# Socket.net
KiCad netlist of a schematic drawn in EAGLE
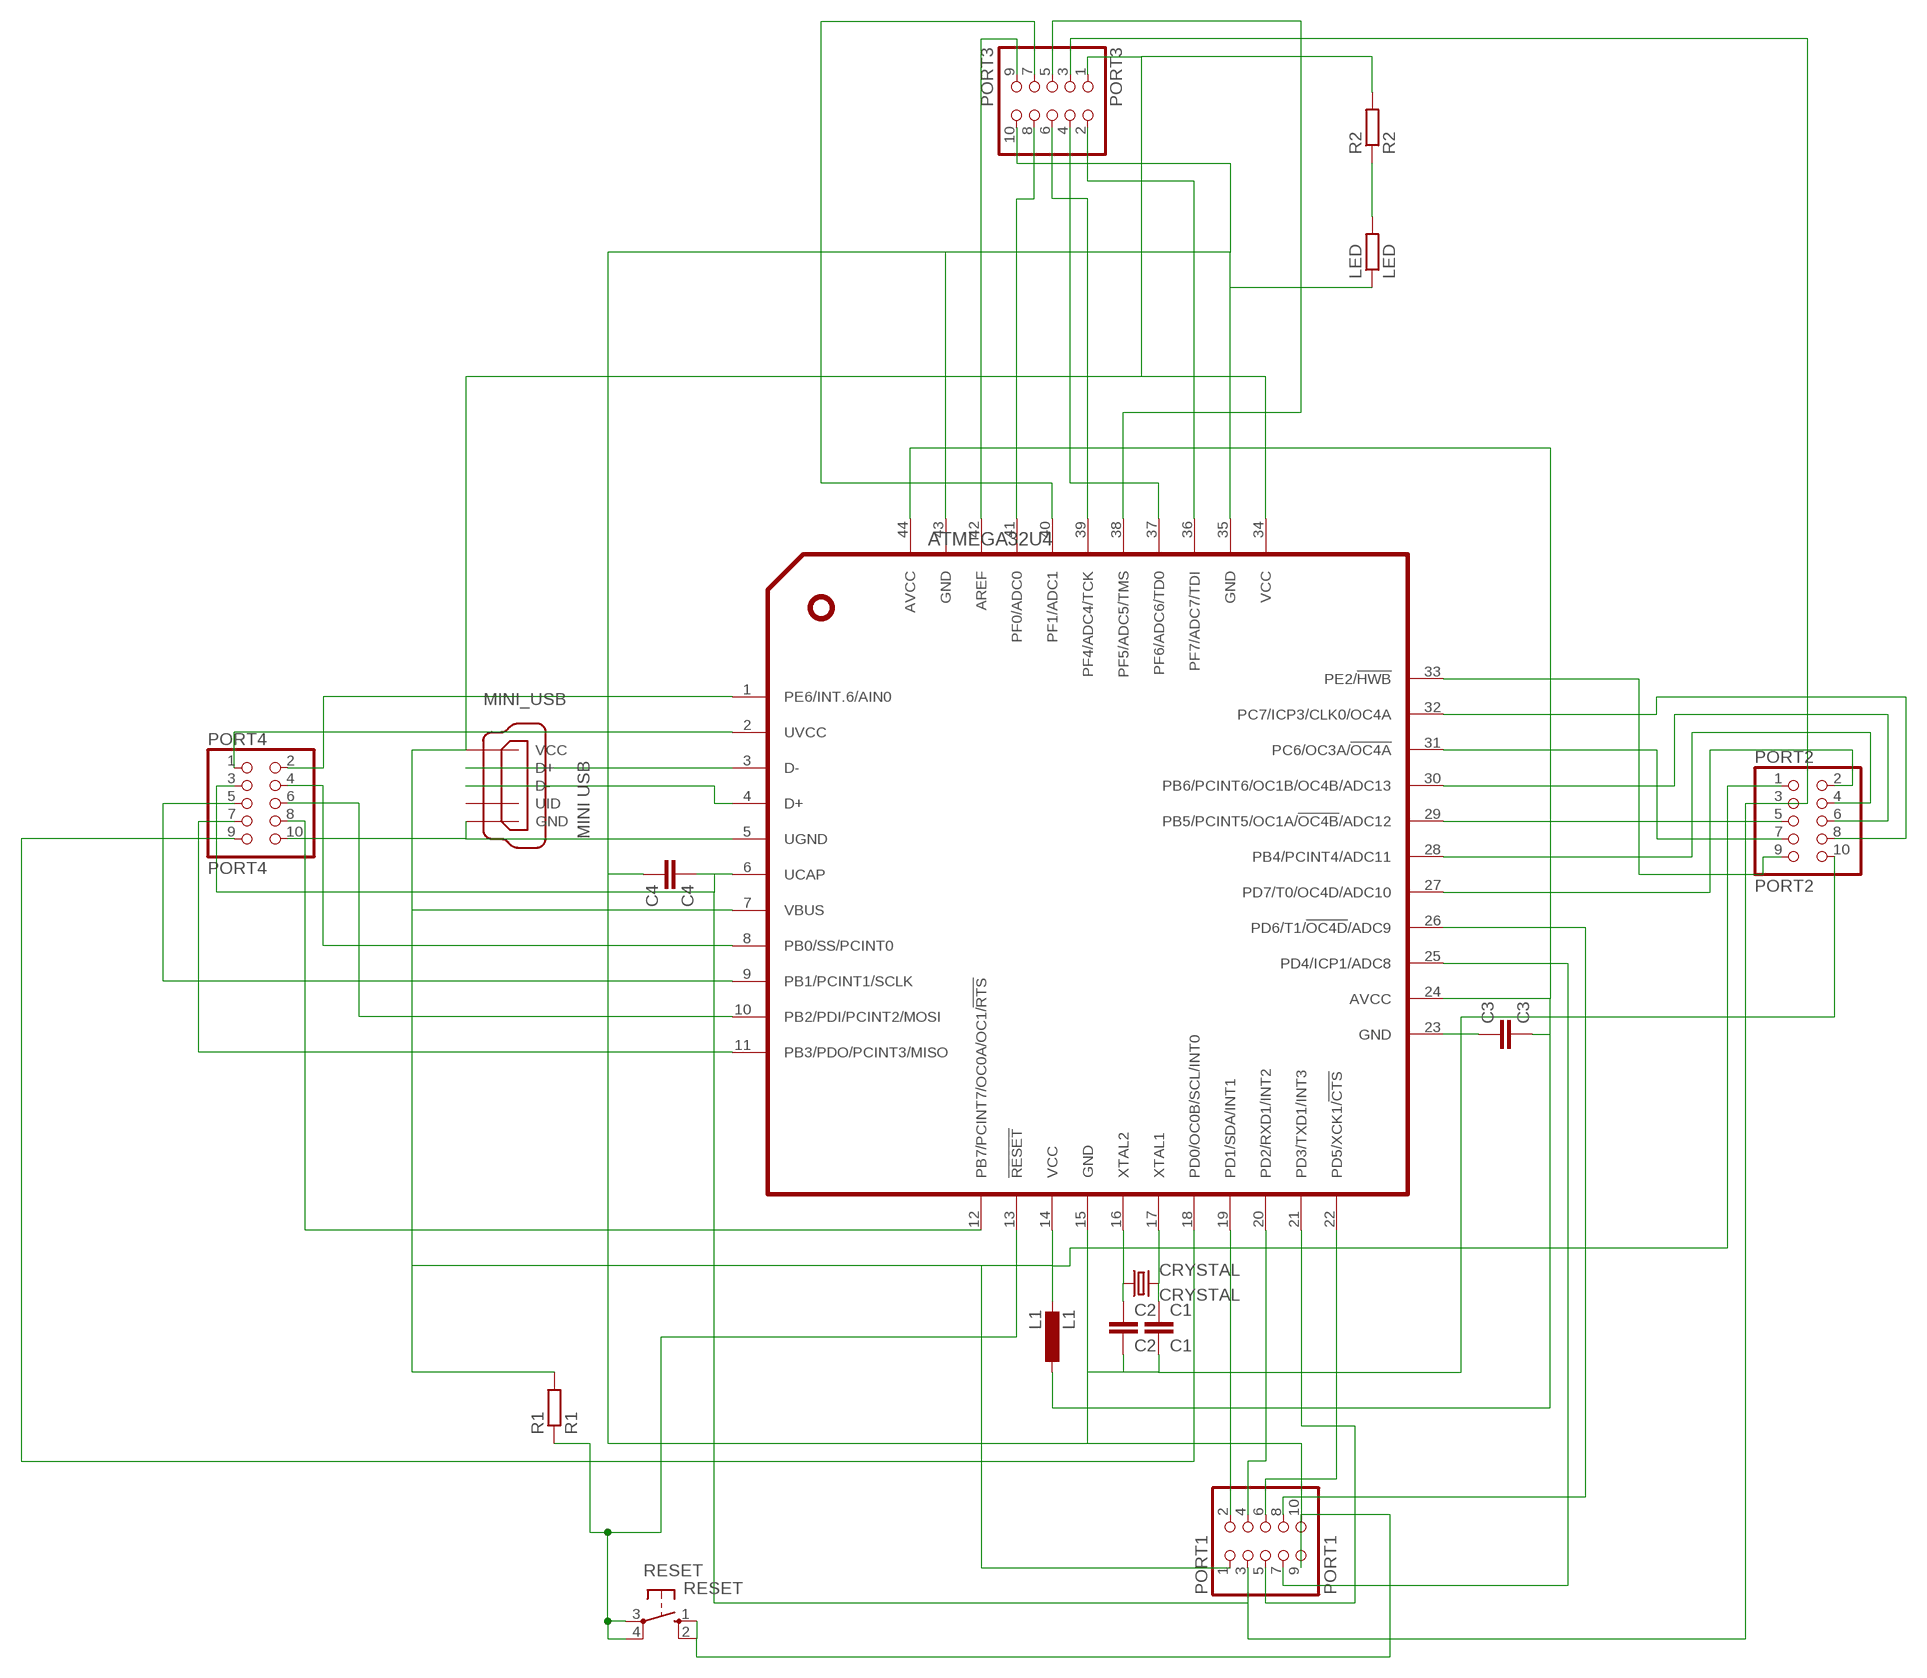
[diagram p0: schematic, sheet 1]

(export (version "E")
  (design (tool "Eeschema 10.0.6"))
  (components
    (comp (ref "ATMEGA32U4")
      (value "ATMEGA32U4")
      (footprint "eagle-import:TQFP44")
      (libsource (lib "eagle-import") (part "AT-MEGA16/32-U4"))
    )
    (comp (ref "C1")
      (value "C1")
      (footprint "eagle-import:C0603")
      (libsource (lib "eagle-import") (part "C-EUC0603"))
    )
    (comp (ref "C2")
      (value "C2")
      (footprint "eagle-import:C0603")
      (libsource (lib "eagle-import") (part "C-EUC0603"))
    )
    (comp (ref "C3")
      (value "C3")
      (footprint "eagle-import:C0603")
      (libsource (lib "eagle-import") (part "C-EUC0603"))
    )
    (comp (ref "C4")
      (value "C4")
      (footprint "eagle-import:C0603")
      (libsource (lib "eagle-import") (part "C-EUC0603"))
    )
    (comp (ref "CRYSTAL")
      (value "CRYSTAL")
      (footprint "eagle-import:HC49UP")
      (libsource (lib "eagle-import") (part "CRYSTALHC49UP"))
    )
    (comp (ref "L1")
      (value "L1")
      (footprint "eagle-import:L2012C")
      (libsource (lib "eagle-import") (part "L-EUL2012C"))
    )
    (comp (ref "LED")
      (value "LED")
      (footprint "eagle-import:R0603")
      (libsource (lib "eagle-import") (part "R-EU_R0603"))
    )
    (comp (ref "MINI_USB")
      (value "MINI USB")
      (footprint "eagle-import:UX60-MB-5S8")
      (libsource (lib "eagle-import") (part "MINI-USB-UX60-MB-5S8"))
    )
    (comp (ref "PORT1")
      (value "PORT1")
      (footprint "eagle-import:2X05")
      (libsource (lib "eagle-import") (part "PINHD-2X5"))
    )
    (comp (ref "PORT2")
      (value "PORT2")
      (footprint "eagle-import:2X05")
      (libsource (lib "eagle-import") (part "PINHD-2X5"))
    )
    (comp (ref "PORT3")
      (value "PORT3")
      (footprint "eagle-import:2X05")
      (libsource (lib "eagle-import") (part "PINHD-2X5"))
    )
    (comp (ref "PORT4")
      (value "PORT4")
      (footprint "eagle-import:2X05")
      (libsource (lib "eagle-import") (part "PINHD-2X5"))
    )
    (comp (ref "R1")
      (value "R1")
      (footprint "eagle-import:R0603")
      (libsource (lib "eagle-import") (part "R-EU_R0603"))
    )
    (comp (ref "R2")
      (value "R2")
      (footprint "eagle-import:R0603")
      (libsource (lib "eagle-import") (part "R-EU_R0603"))
    )
    (comp (ref "RESET")
      (value "RESET")
      (footprint "eagle-import:B3F-10XX")
      (fields (field (name "MPN") "B3F-1000"))
      (libsource (lib "eagle-import") (part "10-XX"))
    )
  )
  (nets
    (net (code "1") (name "Net-(ATMEGA32U4-AREF)") (class "Default")
      (node (ref "ATMEGA32U4") (pin "42") (pinfunction "AREF_42") (pintype "bidirectional"))
      (node (ref "PORT3") (pin "9") (pinfunction "9_9") (pintype "passive"))
    )
    (net (code "2") (name "Net-(ATMEGA32U4-AVCC-Pad24)") (class "Default")
      (node (ref "ATMEGA32U4") (pin "24") (pinfunction "AVCC_24") (pintype "power_in"))
      (node (ref "ATMEGA32U4") (pin "44") (pinfunction "AVCC_44") (pintype "power_in"))
      (node (ref "C3") (pin "2") (pinfunction "2_2") (pintype "passive"))
      (node (ref "L1") (pin "1") (pinfunction "1_1") (pintype "passive"))
    )
    (net (code "3") (name "Net-(ATMEGA32U4-D+)") (class "Default")
      (node (ref "ATMEGA32U4") (pin "4") (pinfunction "D+_4") (pintype "bidirectional"))
      (node (ref "MINI_USB") (pin "D-") (pinfunction "D-_D-") (pintype "input"))
    )
    (net (code "4") (name "Net-(ATMEGA32U4-D-)") (class "Default")
      (node (ref "ATMEGA32U4") (pin "3") (pinfunction "D-_3") (pintype "bidirectional"))
      (node (ref "MINI_USB") (pin "D+") (pinfunction "D+_D+") (pintype "input"))
    )
    (net (code "5") (name "Net-(ATMEGA32U4-PB0{slash}SS{slash}PCINT0)") (class "Default")
      (node (ref "ATMEGA32U4") (pin "8") (pinfunction "PB0/SS/PCINT0_8") (pintype "bidirectional"))
      (node (ref "PORT4") (pin "4") (pinfunction "4_4") (pintype "passive"))
    )
    (net (code "6") (name "Net-(ATMEGA32U4-PB1{slash}PCINT1{slash}SCLK)") (class "Default")
      (node (ref "ATMEGA32U4") (pin "9") (pinfunction "PB1/PCINT1/SCLK_9") (pintype "bidirectional"))
      (node (ref "PORT4") (pin "5") (pinfunction "5_5") (pintype "passive"))
    )
    (net (code "7") (name "Net-(ATMEGA32U4-PB2{slash}PDI{slash}PCINT2{slash}MOSI)") (class "Default")
      (node (ref "ATMEGA32U4") (pin "10") (pinfunction "PB2/PDI/PCINT2/MOSI_10") (pintype "bidirectional"))
      (node (ref "PORT4") (pin "6") (pinfunction "6_6") (pintype "passive"))
    )
    (net (code "8") (name "Net-(ATMEGA32U4-PB3{slash}PDO{slash}PCINT3{slash}MISO)") (class "Default")
      (node (ref "ATMEGA32U4") (pin "11") (pinfunction "PB3/PDO/PCINT3/MISO_11") (pintype "bidirectional"))
      (node (ref "PORT4") (pin "7") (pinfunction "7_7") (pintype "passive"))
    )
    (net (code "9") (name "Net-(ATMEGA32U4-PB4{slash}PCINT4{slash}ADC11)") (class "Default")
      (node (ref "ATMEGA32U4") (pin "28") (pinfunction "PB4/PCINT4/ADC11_28") (pintype "bidirectional"))
      (node (ref "PORT2") (pin "4") (pinfunction "4_4") (pintype "passive"))
    )
    (net (code "10") (name "Net-(ATMEGA32U4-PB5{slash}PCINT5{slash}OC1A{slash}~{OC4B}{slash}ADC12)") (class "Default")
      (node (ref "ATMEGA32U4") (pin "29") (pinfunction "PB5/PCINT5/OC1A/~{OC4B}/ADC12_29") (pintype "bidirectional"))
      (node (ref "PORT2") (pin "5") (pinfunction "5_5") (pintype "passive"))
    )
    (net (code "11") (name "Net-(ATMEGA32U4-PB6{slash}PCINT6{slash}OC1B{slash}OC4B{slash}ADC13)") (class "Default")
      (node (ref "ATMEGA32U4") (pin "30") (pinfunction "PB6/PCINT6/OC1B/OC4B/ADC13_30") (pintype "bidirectional"))
      (node (ref "PORT2") (pin "6") (pinfunction "6_6") (pintype "passive"))
    )
    (net (code "12") (name "Net-(ATMEGA32U4-PB7{slash}PCINT7{slash}OC0A{slash}OC1{slash}~{RTS})") (class "Default")
      (node (ref "ATMEGA32U4") (pin "12") (pinfunction "PB7/PCINT7/OC0A/OC1/~{RTS}_12") (pintype "bidirectional"))
      (node (ref "PORT4") (pin "8") (pinfunction "8_8") (pintype "passive"))
    )
    (net (code "13") (name "Net-(ATMEGA32U4-PC6{slash}OC3A{slash}~{OC4A})") (class "Default")
      (node (ref "ATMEGA32U4") (pin "31") (pinfunction "PC6/OC3A/~{OC4A}_31") (pintype "bidirectional"))
      (node (ref "PORT2") (pin "7") (pinfunction "7_7") (pintype "passive"))
    )
    (net (code "14") (name "Net-(ATMEGA32U4-PC7{slash}ICP3{slash}CLK0{slash}OC4A)") (class "Default")
      (node (ref "ATMEGA32U4") (pin "32") (pinfunction "PC7/ICP3/CLK0/OC4A_32") (pintype "bidirectional"))
      (node (ref "PORT2") (pin "8") (pinfunction "8_8") (pintype "passive"))
    )
    (net (code "15") (name "Net-(ATMEGA32U4-PD0{slash}OC0B{slash}SCL{slash}INT0)") (class "Default")
      (node (ref "ATMEGA32U4") (pin "18") (pinfunction "PD0/OC0B/SCL/INT0_18") (pintype "bidirectional"))
      (node (ref "PORT4") (pin "9") (pinfunction "9_9") (pintype "passive"))
    )
    (net (code "16") (name "Net-(ATMEGA32U4-PD1{slash}SDA{slash}INT1)") (class "Default")
      (node (ref "ATMEGA32U4") (pin "19") (pinfunction "PD1/SDA/INT1_19") (pintype "bidirectional"))
      (node (ref "PORT1") (pin "2") (pinfunction "2_2") (pintype "passive"))
    )
    (net (code "17") (name "Net-(ATMEGA32U4-PD2{slash}RXD1{slash}INT2)") (class "Default")
      (node (ref "ATMEGA32U4") (pin "20") (pinfunction "PD2/RXD1/INT2_20") (pintype "bidirectional"))
      (node (ref "PORT1") (pin "4") (pinfunction "4_4") (pintype "passive"))
    )
    (net (code "18") (name "Net-(ATMEGA32U4-PD3{slash}TXD1{slash}INT3)") (class "Default")
      (node (ref "ATMEGA32U4") (pin "21") (pinfunction "PD3/TXD1/INT3_21") (pintype "bidirectional"))
      (node (ref "PORT1") (pin "5") (pinfunction "5_5") (pintype "passive"))
    )
    (net (code "19") (name "Net-(ATMEGA32U4-PD4{slash}ICP1{slash}ADC8)") (class "Default")
      (node (ref "ATMEGA32U4") (pin "25") (pinfunction "PD4/ICP1/ADC8_25") (pintype "bidirectional"))
      (node (ref "PORT1") (pin "7") (pinfunction "7_7") (pintype "passive"))
    )
    (net (code "20") (name "Net-(ATMEGA32U4-PD5{slash}XCK1{slash}~{CTS})") (class "Default")
      (node (ref "ATMEGA32U4") (pin "22") (pinfunction "PD5/XCK1/~{CTS}_22") (pintype "bidirectional"))
      (node (ref "PORT1") (pin "6") (pinfunction "6_6") (pintype "passive"))
    )
    (net (code "21") (name "Net-(ATMEGA32U4-PD6{slash}T1{slash}~{OC4D}{slash}ADC9)") (class "Default")
      (node (ref "ATMEGA32U4") (pin "26") (pinfunction "PD6/T1/~{OC4D}/ADC9_26") (pintype "bidirectional"))
      (node (ref "PORT1") (pin "8") (pinfunction "8_8") (pintype "passive"))
    )
    (net (code "22") (name "Net-(ATMEGA32U4-PD7{slash}T0{slash}OC4D{slash}ADC10)") (class "Default")
      (node (ref "ATMEGA32U4") (pin "27") (pinfunction "PD7/T0/OC4D/ADC10_27") (pintype "bidirectional"))
      (node (ref "PORT2") (pin "2") (pinfunction "2_2") (pintype "passive"))
    )
    (net (code "23") (name "Net-(ATMEGA32U4-PE2{slash}~{HWB})") (class "Default")
      (node (ref "ATMEGA32U4") (pin "33") (pinfunction "PE2/~{HWB}_33") (pintype "bidirectional"))
      (node (ref "PORT2") (pin "9") (pinfunction "9_9") (pintype "passive"))
    )
    (net (code "24") (name "Net-(ATMEGA32U4-PE6{slash}INT.6{slash}AIN0)") (class "Default")
      (node (ref "ATMEGA32U4") (pin "1") (pinfunction "PE6/INT.6/AIN0_1") (pintype "bidirectional"))
      (node (ref "PORT4") (pin "2") (pinfunction "2_2") (pintype "passive"))
    )
    (net (code "25") (name "Net-(ATMEGA32U4-PF0{slash}ADC0)") (class "Default")
      (node (ref "ATMEGA32U4") (pin "41") (pinfunction "PF0/ADC0_41") (pintype "bidirectional"))
      (node (ref "PORT3") (pin "8") (pinfunction "8_8") (pintype "passive"))
    )
    (net (code "26") (name "Net-(ATMEGA32U4-PF1{slash}ADC1)") (class "Default")
      (node (ref "ATMEGA32U4") (pin "40") (pinfunction "PF1/ADC1_40") (pintype "bidirectional"))
      (node (ref "PORT3") (pin "7") (pinfunction "7_7") (pintype "passive"))
    )
    (net (code "27") (name "Net-(ATMEGA32U4-PF4{slash}ADC4{slash}TCK)") (class "Default")
      (node (ref "ATMEGA32U4") (pin "39") (pinfunction "PF4/ADC4/TCK_39") (pintype "bidirectional"))
      (node (ref "PORT3") (pin "6") (pinfunction "6_6") (pintype "passive"))
    )
    (net (code "28") (name "Net-(ATMEGA32U4-PF5{slash}ADC5{slash}TMS)") (class "Default")
      (node (ref "ATMEGA32U4") (pin "38") (pinfunction "PF5/ADC5/TMS_38") (pintype "bidirectional"))
      (node (ref "PORT3") (pin "5") (pinfunction "5_5") (pintype "passive"))
    )
    (net (code "29") (name "Net-(ATMEGA32U4-PF6{slash}ADC6{slash}TD0)") (class "Default")
      (node (ref "ATMEGA32U4") (pin "37") (pinfunction "PF6/ADC6/TD0_37") (pintype "bidirectional"))
      (node (ref "PORT3") (pin "4") (pinfunction "4_4") (pintype "passive"))
    )
    (net (code "30") (name "Net-(ATMEGA32U4-PF7{slash}ADC7{slash}TDI)") (class "Default")
      (node (ref "ATMEGA32U4") (pin "36") (pinfunction "PF7/ADC7/TDI_36") (pintype "bidirectional"))
      (node (ref "PORT3") (pin "2") (pinfunction "2_2") (pintype "passive"))
    )
    (net (code "31") (name "Net-(ATMEGA32U4-UCAP)") (class "Default")
      (node (ref "ATMEGA32U4") (pin "6") (pinfunction "UCAP_6") (pintype "bidirectional"))
      (node (ref "C4") (pin "1") (pinfunction "1_1") (pintype "passive"))
      (node (ref "PORT1") (pin "3") (pinfunction "3_3") (pintype "passive"))
      (node (ref "PORT2") (pin "3") (pinfunction "3_3") (pintype "passive"))
      (node (ref "PORT3") (pin "3") (pinfunction "3_3") (pintype "passive"))
      (node (ref "PORT4") (pin "3") (pinfunction "3_3") (pintype "passive"))
    )
    (net (code "32") (name "Net-(ATMEGA32U4-UGND)") (class "Default")
      (node (ref "ATMEGA32U4") (pin "15") (pinfunction "GND_15") (pintype "power_in"))
      (node (ref "ATMEGA32U4") (pin "23") (pinfunction "GND_23") (pintype "power_in"))
      (node (ref "ATMEGA32U4") (pin "35") (pinfunction "GND_35") (pintype "power_in"))
      (node (ref "ATMEGA32U4") (pin "43") (pinfunction "GND_43") (pintype "power_in"))
      (node (ref "ATMEGA32U4") (pin "5") (pinfunction "UGND_5") (pintype "power_in"))
      (node (ref "C1") (pin "2") (pinfunction "2_2") (pintype "passive"))
      (node (ref "C2") (pin "2") (pinfunction "2_2") (pintype "passive"))
      (node (ref "C3") (pin "1") (pinfunction "1_1") (pintype "passive"))
      (node (ref "C4") (pin "2") (pinfunction "2_2") (pintype "passive"))
      (node (ref "LED") (pin "1") (pinfunction "1_1") (pintype "passive"))
      (node (ref "MINI_USB") (pin "GND") (pinfunction "GND_GND") (pintype "input"))
      (node (ref "MINI_USB") (pin "GND1") (pinfunction "GND_GND1") (pintype "input"))
      (node (ref "MINI_USB") (pin "GND2") (pinfunction "GND_GND2") (pintype "input"))
      (node (ref "MINI_USB") (pin "GND3") (pinfunction "GND_GND3") (pintype "input"))
      (node (ref "MINI_USB") (pin "GND4") (pinfunction "GND_GND4") (pintype "input"))
      (node (ref "PORT1") (pin "10") (pinfunction "10_10") (pintype "passive"))
      (node (ref "PORT1") (pin "9") (pinfunction "9_9") (pintype "passive"))
      (node (ref "PORT2") (pin "10") (pinfunction "10_10") (pintype "passive"))
      (node (ref "PORT3") (pin "10") (pinfunction "10_10") (pintype "passive"))
      (node (ref "PORT4") (pin "10") (pinfunction "10_10") (pintype "passive"))
      (node (ref "RESET") (pin "1") (pinfunction "S_1") (pintype "passive"))
      (node (ref "RESET") (pin "2") (pinfunction "S1_2") (pintype "passive"))
    )
    (net (code "33") (name "Net-(ATMEGA32U4-UVCC)") (class "Default")
      (node (ref "ATMEGA32U4") (pin "14") (pinfunction "VCC_14") (pintype "power_in"))
      (node (ref "ATMEGA32U4") (pin "2") (pinfunction "UVCC_2") (pintype "power_in"))
      (node (ref "ATMEGA32U4") (pin "34") (pinfunction "VCC_34") (pintype "power_in"))
      (node (ref "ATMEGA32U4") (pin "7") (pinfunction "VBUS_7") (pintype "input"))
      (node (ref "L1") (pin "2") (pinfunction "2_2") (pintype "passive"))
      (node (ref "MINI_USB") (pin "VCC") (pinfunction "VCC_VCC") (pintype "input"))
      (node (ref "PORT1") (pin "1") (pinfunction "1_1") (pintype "passive"))
      (node (ref "PORT2") (pin "1") (pinfunction "1_1") (pintype "passive"))
      (node (ref "PORT3") (pin "1") (pinfunction "1_1") (pintype "passive"))
      (node (ref "PORT4") (pin "1") (pinfunction "1_1") (pintype "passive"))
      (node (ref "R1") (pin "2") (pinfunction "2_2") (pintype "passive"))
      (node (ref "R2") (pin "2") (pinfunction "2_2") (pintype "passive"))
    )
    (net (code "34") (name "Net-(ATMEGA32U4-XTAL1)") (class "Default")
      (node (ref "ATMEGA32U4") (pin "17") (pinfunction "XTAL1_17") (pintype "bidirectional"))
      (node (ref "C1") (pin "1") (pinfunction "1_1") (pintype "passive"))
      (node (ref "CRYSTAL") (pin "2") (pinfunction "2_2") (pintype "passive"))
    )
    (net (code "35") (name "Net-(ATMEGA32U4-XTAL2)") (class "Default")
      (node (ref "ATMEGA32U4") (pin "16") (pinfunction "XTAL2_16") (pintype "bidirectional"))
      (node (ref "C2") (pin "1") (pinfunction "1_1") (pintype "passive"))
      (node (ref "CRYSTAL") (pin "1") (pinfunction "1_1") (pintype "passive"))
    )
    (net (code "36") (name "Net-(ATMEGA32U4-~{RESET})") (class "Default")
      (node (ref "ATMEGA32U4") (pin "13") (pinfunction "~{RESET}_13") (pintype "input"))
      (node (ref "R1") (pin "1") (pinfunction "1_1") (pintype "passive"))
      (node (ref "RESET") (pin "3") (pinfunction "P_3") (pintype "passive"))
      (node (ref "RESET") (pin "4") (pinfunction "P1_4") (pintype "passive"))
    )
    (net (code "37") (name "Net-(LED-Pad2)") (class "Default")
      (node (ref "LED") (pin "2") (pinfunction "2_2") (pintype "passive"))
      (node (ref "R2") (pin "1") (pinfunction "1_1") (pintype "passive"))
    )
    (net (code "38") (name "unconnected-(MINI_USB-PadUID)") (class "Default")
      (node (ref "MINI_USB") (pin "UID") (pinfunction "UID_UID") (pintype "input"))
    )
  )
)
